# LoRa_RFM98W_Shield.net
KiCad netlist of a schematic drawn in EAGLE
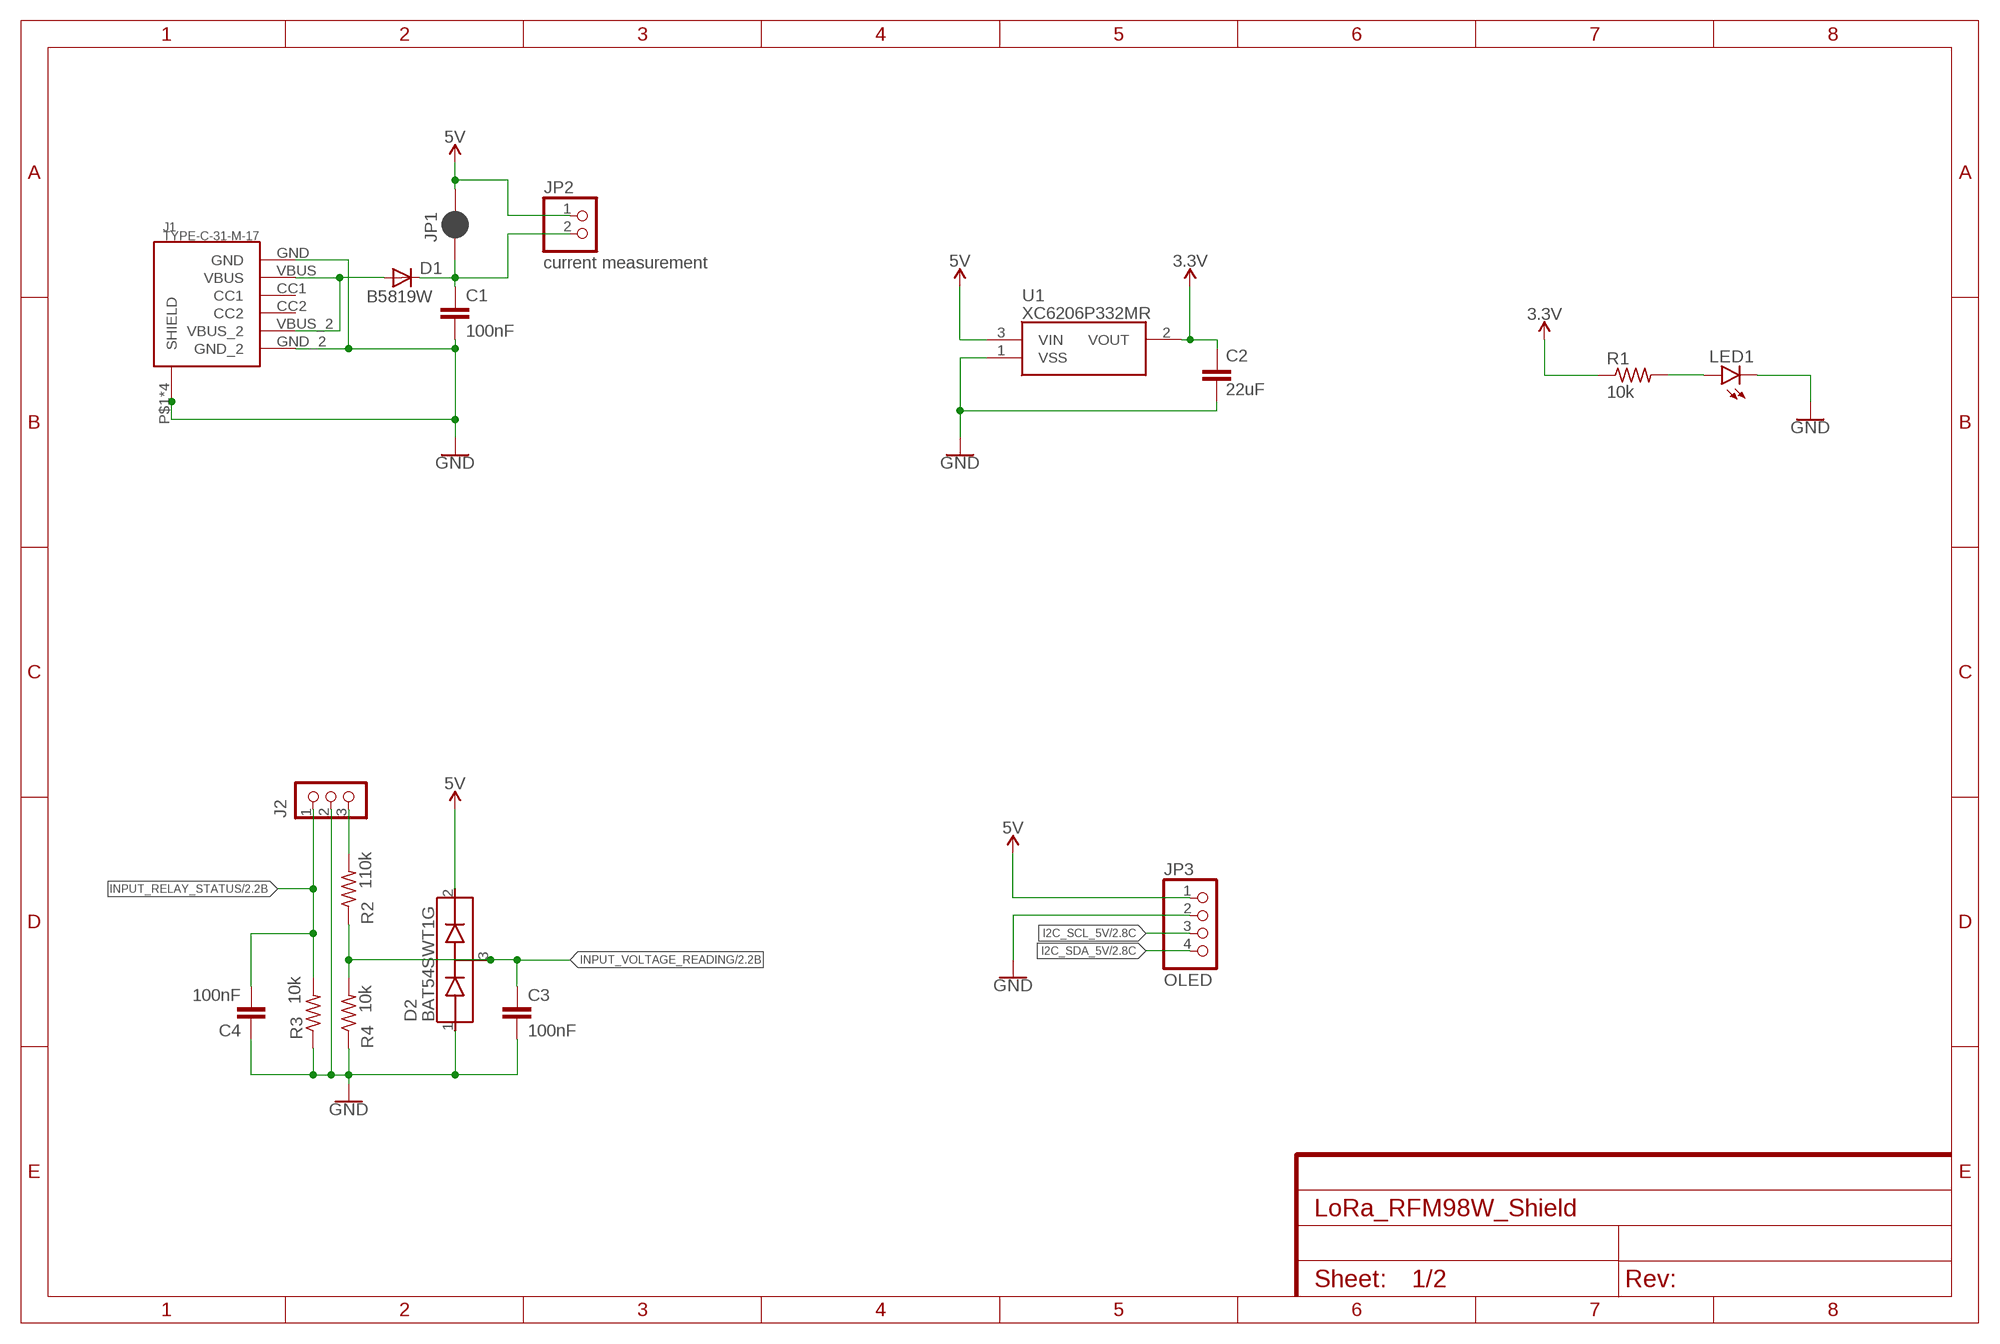
[diagram p0: schematic, sheet 1]
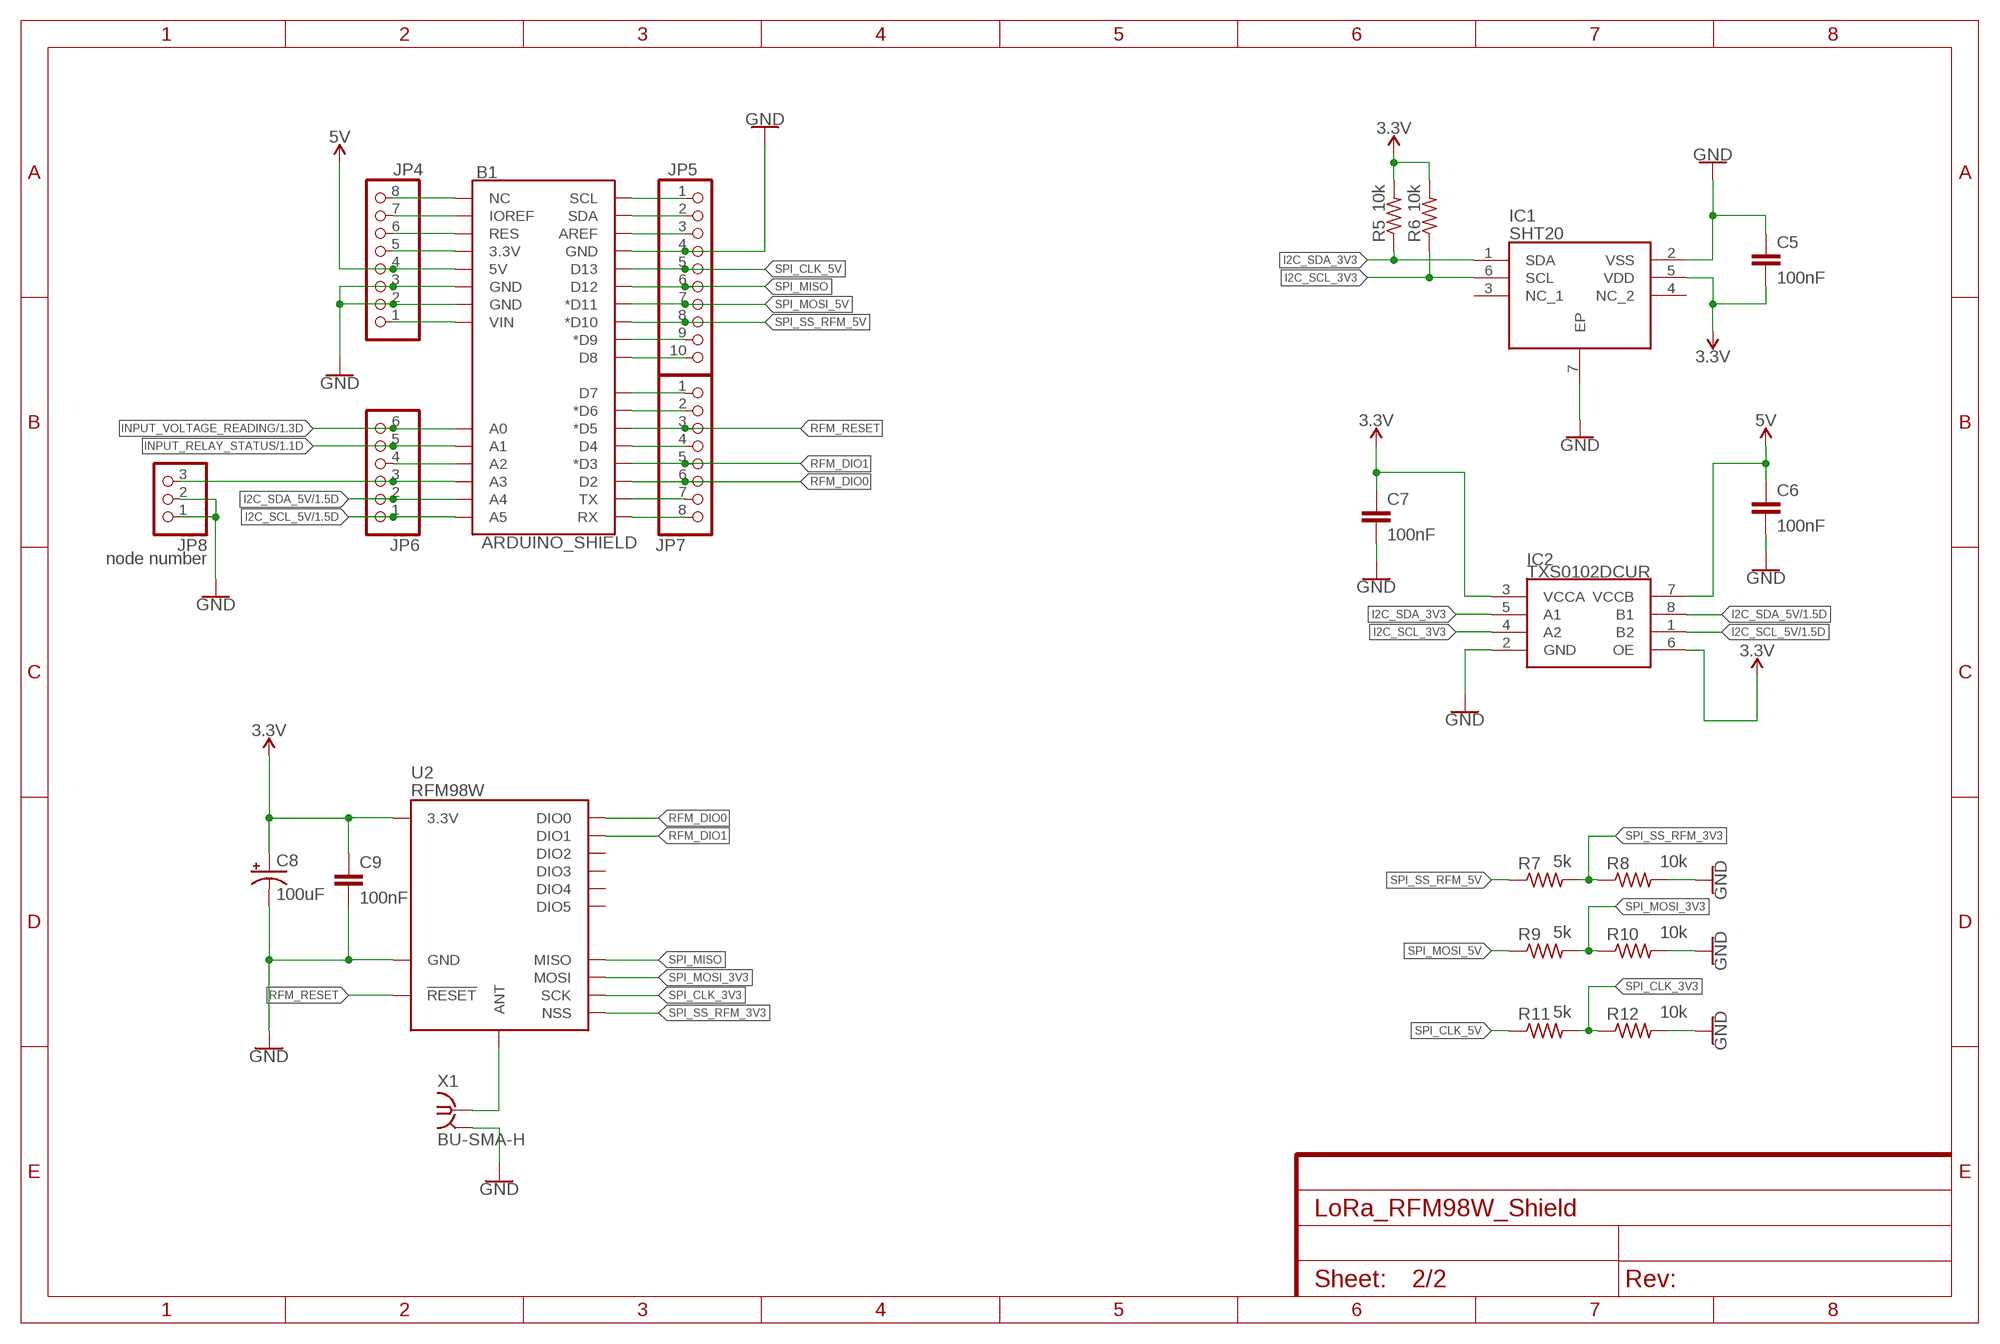
[diagram p1: schematic, sheet 2]

(export (version "E")
  (design (tool "Eeschema 10.0.6"))
  (components
    (comp (ref "B1")
      (value "ARDUINO_SHIELD")
      (footprint "eagle-import:UNO_R3_SHIELD_NOLABELS_LOCK")
      (libsource (lib "eagle-import") (part "ARDUINO_UNO_R3_SHIELDUNO_R3_SHIELD_NOLABELS_LOCK"))
    )
    (comp (ref "C5")
      (value "100nF")
      (footprint "eagle-import:C0603")
      (libsource (lib "eagle-import") (part "C-EUC0603"))
    )
    (comp (ref "C6")
      (value "100nF")
      (footprint "eagle-import:C0603")
      (libsource (lib "eagle-import") (part "C-EUC0603"))
    )
    (comp (ref "C7")
      (value "100nF")
      (footprint "eagle-import:C0603")
      (libsource (lib "eagle-import") (part "C-EUC0603"))
    )
    (comp (ref "C8")
      (value "100uF")
      (footprint "eagle-import:SMC_B")
      (libsource (lib "eagle-import") (part "CPOL-USSMCB"))
    )
    (comp (ref "C9")
      (value "100nF")
      (footprint "eagle-import:C0603")
      (libsource (lib "eagle-import") (part "C-EUC0603"))
    )
    (comp (ref "IC1")
      (value "SHT20")
      (footprint "eagle-import:SON100P300X300X110-7N")
      (fields (field (name "LCSC_PART_NUMBER") "C53865"))
      (libsource (lib "eagle-import") (part "SHT20"))
    )
    (comp (ref "IC2")
      (value "TXS0102DCUR")
      (footprint "eagle-import:SOP50P310X90-8N")
      (fields (field (name "LCSC_PART_NUMBER") "C53434"))
      (libsource (lib "eagle-import") (part "TXS0102DCUR"))
    )
    (comp (ref "JP4")
      (value "PINHD-1X8/OCT")
      (footprint "eagle-import:1X08_OCT")
      (libsource (lib "eagle-import") (part "PINHD-1X8/OCT"))
    )
    (comp (ref "JP5")
      (value "PINHD-1X10/OCT")
      (footprint "eagle-import:1X10_OCT")
      (libsource (lib "eagle-import") (part "PINHD-1X10/OCT"))
    )
    (comp (ref "JP6")
      (value "PINHD-1X6/OCT")
      (footprint "eagle-import:1X06_OCT")
      (libsource (lib "eagle-import") (part "PINHD-1X6/OCT"))
    )
    (comp (ref "JP7")
      (value "PINHD-1X8/OCT")
      (footprint "eagle-import:1X08_OCT")
      (libsource (lib "eagle-import") (part "PINHD-1X8/OCT"))
    )
    (comp (ref "JP8")
      (value "node number")
      (footprint "eagle-import:1X03_OCT")
      (libsource (lib "eagle-import") (part "PINHD-1X3/OCT"))
    )
    (comp (ref "R5")
      (value "10k")
      (footprint "eagle-import:R0603")
      (libsource (lib "eagle-import") (part "R-US_R0603"))
    )
    (comp (ref "R6")
      (value "10k")
      (footprint "eagle-import:R0603")
      (libsource (lib "eagle-import") (part "R-US_R0603"))
    )
    (comp (ref "R7")
      (value "5k")
      (footprint "eagle-import:R0603")
      (libsource (lib "eagle-import") (part "R-US_R0603"))
    )
    (comp (ref "R8")
      (value "10k")
      (footprint "eagle-import:R0603")
      (libsource (lib "eagle-import") (part "R-US_R0603"))
    )
    (comp (ref "R9")
      (value "5k")
      (footprint "eagle-import:R0603")
      (libsource (lib "eagle-import") (part "R-US_R0603"))
    )
    (comp (ref "R10")
      (value "10k")
      (footprint "eagle-import:R0603")
      (libsource (lib "eagle-import") (part "R-US_R0603"))
    )
    (comp (ref "R11")
      (value "5k")
      (footprint "eagle-import:R0603")
      (libsource (lib "eagle-import") (part "R-US_R0603"))
    )
    (comp (ref "R12")
      (value "10k")
      (footprint "eagle-import:R0603")
      (libsource (lib "eagle-import") (part "R-US_R0603"))
    )
    (comp (ref "U2")
      (value "RFM98W")
      (footprint "eagle-import:RFM95_96_97_98W")
      (libsource (lib "eagle-import") (part "RFM95W"))
    )
    (comp (ref "X1")
      (value "BU-SMA-H")
      (footprint "eagle-import:BU-SMA-H")
      (libsource (lib "eagle-import") (part "BU-SMA-H"))
    )
    (comp (ref "C1")
      (value "100nF")
      (footprint "eagle-import:C0603")
      (libsource (lib "eagle-import") (part "C-EUC0603"))
    )
    (comp (ref "C2")
      (value "22uF")
      (footprint "eagle-import:C0805")
      (libsource (lib "eagle-import") (part "C-EUC0805"))
    )
    (comp (ref "C3")
      (value "100nF")
      (footprint "eagle-import:C0603")
      (libsource (lib "eagle-import") (part "C-EUC0603"))
    )
    (comp (ref "C4")
      (value "100nF")
      (footprint "eagle-import:C0603")
      (libsource (lib "eagle-import") (part "C-EUC0603"))
    )
    (comp (ref "D1")
      (value "B5819W")
      (footprint "eagle-import:SOD-123")
      (libsource (lib "eagle-import") (part "DIODE-SOD-123"))
    )
    (comp (ref "D2")
      (value "BAT54SWT1G")
      (footprint "eagle-import:SOT65P220X100-3N")
      (fields (field (name "LCSC_PART_NUMBER") "C78260"))
      (libsource (lib "eagle-import") (part "BAT54SWT1G"))
    )
    (comp (ref "J1")
      (value "TYPE-C-31-M-17")
      (footprint "eagle-import:TYPE-C-31-M-17")
      (libsource (lib "eagle-import") (part "TYPE-C-31-M-17"))
    )
    (comp (ref "J2")
      (value "CON_TERMINAL_BLOCK_03-5MM")
      (footprint "eagle-import:TERMINAL_BLOCK_3P_5")
      (libsource (lib "eagle-import") (part "CON_TERMINAL_BLOCK_03-5MM"))
    )
    (comp (ref "JP1")
      (value "JUMPER-SMT_2_NC_PASTE_SILK")
      (footprint "eagle-import:SMT-JUMPER_2_NC_PASTE_SILK")
      (libsource (lib "eagle-import") (part "JUMPER-SMT_2_NC_PASTE_SILK"))
    )
    (comp (ref "JP2")
      (value "current measurement")
      (footprint "eagle-import:1X02_OCT")
      (libsource (lib "eagle-import") (part "PINHD-1X2/OCT"))
    )
    (comp (ref "JP3")
      (value "OLED")
      (footprint "eagle-import:1X04_OCT")
      (libsource (lib "eagle-import") (part "PINHD-1X4/OCT"))
    )
    (comp (ref "LED1")
      (value "LEDCHIPLED_0805")
      (footprint "eagle-import:CHIPLED_0805")
      (libsource (lib "eagle-import") (part "LEDCHIPLED_0805"))
    )
    (comp (ref "R1")
      (value "10k")
      (footprint "eagle-import:R0603")
      (libsource (lib "eagle-import") (part "R-US_R0603"))
    )
    (comp (ref "R2")
      (value "110k")
      (footprint "eagle-import:R0603")
      (libsource (lib "eagle-import") (part "R-US_R0603"))
    )
    (comp (ref "R3")
      (value "10k")
      (footprint "eagle-import:R0603")
      (libsource (lib "eagle-import") (part "R-US_R0603"))
    )
    (comp (ref "R4")
      (value "10k")
      (footprint "eagle-import:R0603")
      (libsource (lib "eagle-import") (part "R-US_R0603"))
    )
    (comp (ref "U1")
      (value "XC6206P332MR")
      (footprint "eagle-import:SOT95P280X130-3N")
      (libsource (lib "eagle-import") (part "XC6206P332MR"))
    )
  )
  (nets
    (net (code "1") (name "3.3V") (class "Default")
      (node (ref "C2") (pin "2") (pinfunction "2_2") (pintype "passive"))
      (node (ref "C5") (pin "2") (pinfunction "2_2") (pintype "passive"))
      (node (ref "C7") (pin "1") (pinfunction "1_1") (pintype "passive"))
      (node (ref "C8") (pin "+") (pinfunction "+_+") (pintype "passive"))
      (node (ref "C9") (pin "1") (pinfunction "1_1") (pintype "passive"))
      (node (ref "IC1") (pin "5") (pinfunction "VDD_5") (pintype "bidirectional"))
      (node (ref "IC2") (pin "3") (pinfunction "VCCA_3") (pintype "bidirectional"))
      (node (ref "IC2") (pin "6") (pinfunction "OE_6") (pintype "bidirectional"))
      (node (ref "R1") (pin "1") (pinfunction "1_1") (pintype "passive"))
      (node (ref "R5") (pin "2") (pinfunction "2_2") (pintype "passive"))
      (node (ref "R6") (pin "2") (pinfunction "2_2") (pintype "passive"))
      (node (ref "U1") (pin "2") (pinfunction "VOUT_2") (pintype "output"))
      (node (ref "U2") (pin "3.3V") (pinfunction "3.3V_3.3V") (pintype "bidirectional"))
    )
    (net (code "2") (name "5V") (class "Default")
      (node (ref "B1") (pin "5V") (pinfunction "5V_5V") (pintype "bidirectional"))
      (node (ref "C6") (pin "1") (pinfunction "1_1") (pintype "passive"))
      (node (ref "D2") (pin "2") (pinfunction "CATHODE_2") (pintype "bidirectional"))
      (node (ref "IC2") (pin "7") (pinfunction "VCCB_7") (pintype "bidirectional"))
      (node (ref "JP1") (pin "2") (pinfunction "2_2") (pintype "passive"))
      (node (ref "JP2") (pin "1") (pinfunction "1_1") (pintype "passive"))
      (node (ref "JP3") (pin "1") (pinfunction "1_1") (pintype "passive"))
      (node (ref "JP4") (pin "4") (pinfunction "4_4") (pintype "passive"))
      (node (ref "U1") (pin "3") (pinfunction "VIN_3") (pintype "input"))
    )
    (net (code "3") (name "GND") (class "Default")
      (node (ref "B1") (pin "GND@0") (pinfunction "GND_GND@0") (pintype "bidirectional"))
      (node (ref "B1") (pin "GND@1") (pinfunction "GND_GND@1") (pintype "bidirectional"))
      (node (ref "B1") (pin "GND@2") (pinfunction "GND_GND@2") (pintype "bidirectional"))
      (node (ref "C1") (pin "2") (pinfunction "2_2") (pintype "passive"))
      (node (ref "C2") (pin "1") (pinfunction "1_1") (pintype "passive"))
      (node (ref "C3") (pin "2") (pinfunction "2_2") (pintype "passive"))
      (node (ref "C4") (pin "1") (pinfunction "1_1") (pintype "passive"))
      (node (ref "C5") (pin "1") (pinfunction "1_1") (pintype "passive"))
      (node (ref "C6") (pin "2") (pinfunction "2_2") (pintype "passive"))
      (node (ref "C7") (pin "2") (pinfunction "2_2") (pintype "passive"))
      (node (ref "C8") (pin "-") (pinfunction "-_-") (pintype "passive"))
      (node (ref "C9") (pin "2") (pinfunction "2_2") (pintype "passive"))
      (node (ref "D2") (pin "1") (pinfunction "ANODE_1") (pintype "bidirectional"))
      (node (ref "IC1") (pin "2") (pinfunction "VSS_2") (pintype "bidirectional"))
      (node (ref "IC1") (pin "7") (pinfunction "EP_7") (pintype "bidirectional"))
      (node (ref "IC2") (pin "2") (pinfunction "GND_2") (pintype "bidirectional"))
      (node (ref "J1") (pin "GND") (pinfunction "GND_GND") (pintype "bidirectional"))
      (node (ref "J1") (pin "GND_2") (pinfunction "GND_2_GND_2") (pintype "bidirectional"))
      (node (ref "J1") (pin "P$1") (pinfunction "SHIELD_P$1") (pintype "bidirectional"))
      (node (ref "J1") (pin "P$2") (pinfunction "SHIELD_P$2") (pintype "bidirectional"))
      (node (ref "J1") (pin "P$3") (pinfunction "SHIELD_P$3") (pintype "bidirectional"))
      (node (ref "J1") (pin "P$4") (pinfunction "SHIELD_P$4") (pintype "bidirectional"))
      (node (ref "J2") (pin "2") (pinfunction "2_2") (pintype "bidirectional"))
      (node (ref "JP3") (pin "2") (pinfunction "2_2") (pintype "passive"))
      (node (ref "JP4") (pin "2") (pinfunction "2_2") (pintype "passive"))
      (node (ref "JP4") (pin "3") (pinfunction "3_3") (pintype "passive"))
      (node (ref "JP5") (pin "4") (pinfunction "4_4") (pintype "passive"))
      (node (ref "JP8") (pin "1") (pinfunction "1_1") (pintype "passive"))
      (node (ref "JP8") (pin "2") (pinfunction "2_2") (pintype "passive"))
      (node (ref "LED1") (pin "C") (pinfunction "C_C") (pintype "passive"))
      (node (ref "R10") (pin "2") (pinfunction "2_2") (pintype "passive"))
      (node (ref "R12") (pin "2") (pinfunction "2_2") (pintype "passive"))
      (node (ref "R3") (pin "1") (pinfunction "1_1") (pintype "passive"))
      (node (ref "R4") (pin "1") (pinfunction "1_1") (pintype "passive"))
      (node (ref "R8") (pin "2") (pinfunction "2_2") (pintype "passive"))
      (node (ref "U1") (pin "1") (pinfunction "VSS_1") (pintype "power_in"))
      (node (ref "U2") (pin "GND@1") (pinfunction "GND_GND@1") (pintype "bidirectional"))
      (node (ref "U2") (pin "GND@2") (pinfunction "GND_GND@2") (pintype "bidirectional"))
      (node (ref "U2") (pin "GND@3") (pinfunction "GND_GND@3") (pintype "bidirectional"))
      (node (ref "X1") (pin "2") (pinfunction "2_2") (pintype "passive"))
      (node (ref "X1") (pin "3") (pinfunction "2_3") (pintype "passive"))
      (node (ref "X1") (pin "4") (pinfunction "2_4") (pintype "passive"))
      (node (ref "X1") (pin "5") (pinfunction "2_5") (pintype "passive"))
    )
    (net (code "4") (name "I2C_SCL_3V3") (class "Default")
      (node (ref "IC1") (pin "6") (pinfunction "SCL_6") (pintype "bidirectional"))
      (node (ref "IC2") (pin "4") (pinfunction "A2_4") (pintype "bidirectional"))
      (node (ref "R6") (pin "1") (pinfunction "1_1") (pintype "passive"))
    )
    (net (code "5") (name "I2C_SCL_5V") (class "Default")
      (node (ref "B1") (pin "A5") (pinfunction "A5_A5") (pintype "bidirectional"))
      (node (ref "IC2") (pin "1") (pinfunction "B2_1") (pintype "bidirectional"))
      (node (ref "JP3") (pin "3") (pinfunction "3_3") (pintype "passive"))
      (node (ref "JP6") (pin "1") (pinfunction "1_1") (pintype "passive"))
    )
    (net (code "6") (name "I2C_SDA_3V3") (class "Default")
      (node (ref "IC1") (pin "1") (pinfunction "SDA_1") (pintype "bidirectional"))
      (node (ref "IC2") (pin "5") (pinfunction "A1_5") (pintype "bidirectional"))
      (node (ref "R5") (pin "1") (pinfunction "1_1") (pintype "passive"))
    )
    (net (code "7") (name "I2C_SDA_5V") (class "Default")
      (node (ref "B1") (pin "A4") (pinfunction "A4_A4") (pintype "bidirectional"))
      (node (ref "IC2") (pin "8") (pinfunction "B1_8") (pintype "bidirectional"))
      (node (ref "JP3") (pin "4") (pinfunction "4_4") (pintype "passive"))
      (node (ref "JP6") (pin "2") (pinfunction "2_2") (pintype "passive"))
    )
    (net (code "8") (name "INPUT_RELAY_STATUS") (class "Default")
      (node (ref "B1") (pin "A1") (pinfunction "A1_A1") (pintype "bidirectional"))
      (node (ref "C4") (pin "2") (pinfunction "2_2") (pintype "passive"))
      (node (ref "J2") (pin "1") (pinfunction "1_1") (pintype "bidirectional"))
      (node (ref "JP6") (pin "5") (pinfunction "5_5") (pintype "passive"))
      (node (ref "R3") (pin "2") (pinfunction "2_2") (pintype "passive"))
    )
    (net (code "9") (name "INPUT_VOLTAGE_READING") (class "Default")
      (node (ref "B1") (pin "A0") (pinfunction "A0_A0") (pintype "bidirectional"))
      (node (ref "C3") (pin "1") (pinfunction "1_1") (pintype "passive"))
      (node (ref "D2") (pin "3") (pinfunction "CATHODE-ANODE_3") (pintype "bidirectional"))
      (node (ref "JP6") (pin "6") (pinfunction "6_6") (pintype "passive"))
      (node (ref "R2") (pin "1") (pinfunction "1_1") (pintype "passive"))
      (node (ref "R4") (pin "2") (pinfunction "2_2") (pintype "passive"))
    )
    (net (code "10") (name "Net-(B1-*D6)") (class "Default")
      (node (ref "B1") (pin "D6") (pinfunction "*D6_D6") (pintype "bidirectional"))
      (node (ref "JP7") (pin "2") (pinfunction "2_2") (pintype "passive"))
    )
    (net (code "11") (name "Net-(B1-*D9)") (class "Default")
      (node (ref "B1") (pin "D9") (pinfunction "*D9_D9") (pintype "bidirectional"))
      (node (ref "JP5") (pin "9") (pinfunction "9_9") (pintype "passive"))
    )
    (net (code "12") (name "Net-(B1-Pad3.3V)") (class "Default")
      (node (ref "B1") (pin "3.3V") (pinfunction "3.3V_3.3V") (pintype "bidirectional"))
      (node (ref "JP4") (pin "5") (pinfunction "5_5") (pintype "passive"))
    )
    (net (code "13") (name "Net-(B1-PadA2)") (class "Default")
      (node (ref "B1") (pin "A2") (pinfunction "A2_A2") (pintype "bidirectional"))
      (node (ref "JP6") (pin "4") (pinfunction "4_4") (pintype "passive"))
    )
    (net (code "14") (name "Net-(B1-PadA3)") (class "Default")
      (node (ref "B1") (pin "A3") (pinfunction "A3_A3") (pintype "bidirectional"))
      (node (ref "JP6") (pin "3") (pinfunction "3_3") (pintype "passive"))
      (node (ref "JP8") (pin "3") (pinfunction "3_3") (pintype "passive"))
    )
    (net (code "15") (name "Net-(B1-PadAREF)") (class "Default")
      (node (ref "B1") (pin "AREF") (pinfunction "AREF_AREF") (pintype "bidirectional"))
      (node (ref "JP5") (pin "3") (pinfunction "3_3") (pintype "passive"))
    )
    (net (code "16") (name "Net-(B1-PadD4)") (class "Default")
      (node (ref "B1") (pin "D4") (pinfunction "D4_D4") (pintype "bidirectional"))
      (node (ref "JP7") (pin "4") (pinfunction "4_4") (pintype "passive"))
    )
    (net (code "17") (name "Net-(B1-PadD7)") (class "Default")
      (node (ref "B1") (pin "D7") (pinfunction "D7_D7") (pintype "bidirectional"))
      (node (ref "JP7") (pin "1") (pinfunction "1_1") (pintype "passive"))
    )
    (net (code "18") (name "Net-(B1-PadD8)") (class "Default")
      (node (ref "B1") (pin "D8") (pinfunction "D8_D8") (pintype "bidirectional"))
      (node (ref "JP5") (pin "10") (pinfunction "10_10") (pintype "passive"))
    )
    (net (code "19") (name "Net-(B1-PadIOREF)") (class "Default")
      (node (ref "B1") (pin "IOREF") (pinfunction "IOREF_IOREF") (pintype "bidirectional"))
      (node (ref "JP4") (pin "7") (pinfunction "7_7") (pintype "passive"))
    )
    (net (code "20") (name "Net-(B1-PadNC)") (class "Default")
      (node (ref "B1") (pin "NC") (pinfunction "NC_NC") (pintype "bidirectional"))
      (node (ref "JP4") (pin "8") (pinfunction "8_8") (pintype "passive"))
    )
    (net (code "21") (name "Net-(B1-PadRES)") (class "Default")
      (node (ref "B1") (pin "RES") (pinfunction "RES_RES") (pintype "bidirectional"))
      (node (ref "JP4") (pin "6") (pinfunction "6_6") (pintype "passive"))
    )
    (net (code "22") (name "Net-(B1-PadRX)") (class "Default")
      (node (ref "B1") (pin "RX") (pinfunction "RX_RX") (pintype "bidirectional"))
      (node (ref "JP7") (pin "8") (pinfunction "8_8") (pintype "passive"))
    )
    (net (code "23") (name "Net-(B1-PadSCL)") (class "Default")
      (node (ref "B1") (pin "SCL") (pinfunction "SCL_SCL") (pintype "bidirectional"))
      (node (ref "JP5") (pin "1") (pinfunction "1_1") (pintype "passive"))
    )
    (net (code "24") (name "Net-(B1-PadSDA)") (class "Default")
      (node (ref "B1") (pin "SDA") (pinfunction "SDA_SDA") (pintype "bidirectional"))
      (node (ref "JP5") (pin "2") (pinfunction "2_2") (pintype "passive"))
    )
    (net (code "25") (name "Net-(B1-PadTX)") (class "Default")
      (node (ref "B1") (pin "TX") (pinfunction "TX_TX") (pintype "bidirectional"))
      (node (ref "JP7") (pin "7") (pinfunction "7_7") (pintype "passive"))
    )
    (net (code "26") (name "Net-(B1-PadVIN)") (class "Default")
      (node (ref "B1") (pin "VIN") (pinfunction "VIN_VIN") (pintype "bidirectional"))
      (node (ref "JP4") (pin "1") (pinfunction "1_1") (pintype "passive"))
    )
    (net (code "27") (name "Net-(C1-Pad1)") (class "Default")
      (node (ref "C1") (pin "1") (pinfunction "1_1") (pintype "passive"))
      (node (ref "D1") (pin "C") (pinfunction "C_C") (pintype "passive"))
      (node (ref "JP1") (pin "1") (pinfunction "1_1") (pintype "passive"))
      (node (ref "JP2") (pin "2") (pinfunction "2_2") (pintype "passive"))
    )
    (net (code "28") (name "Net-(D1-PadA)") (class "Default")
      (node (ref "D1") (pin "A") (pinfunction "A_A") (pintype "passive"))
      (node (ref "J1") (pin "VBUS") (pinfunction "VBUS_VBUS") (pintype "bidirectional"))
      (node (ref "J1") (pin "VBUS_2") (pinfunction "VBUS_2_VBUS_2") (pintype "bidirectional"))
    )
    (net (code "29") (name "Net-(J2-Pad3)") (class "Default")
      (node (ref "J2") (pin "3") (pinfunction "3_3") (pintype "bidirectional"))
      (node (ref "R2") (pin "2") (pinfunction "2_2") (pintype "passive"))
    )
    (net (code "30") (name "Net-(LED1-PadA)") (class "Default")
      (node (ref "LED1") (pin "A") (pinfunction "A_A") (pintype "passive"))
      (node (ref "R1") (pin "2") (pinfunction "2_2") (pintype "passive"))
    )
    (net (code "31") (name "Net-(U2-PadANT)") (class "Default")
      (node (ref "U2") (pin "ANT") (pinfunction "ANT_ANT") (pintype "bidirectional"))
      (node (ref "X1") (pin "1") (pinfunction "1_1") (pintype "passive"))
    )
    (net (code "32") (name "RFM_DIO0") (class "Default")
      (node (ref "B1") (pin "D2") (pinfunction "D2_D2") (pintype "bidirectional"))
      (node (ref "JP7") (pin "6") (pinfunction "6_6") (pintype "passive"))
      (node (ref "U2") (pin "DIO0") (pinfunction "DIO0_DIO0") (pintype "bidirectional"))
    )
    (net (code "33") (name "RFM_DIO1") (class "Default")
      (node (ref "B1") (pin "D3") (pinfunction "*D3_D3") (pintype "bidirectional"))
      (node (ref "JP7") (pin "5") (pinfunction "5_5") (pintype "passive"))
      (node (ref "U2") (pin "DIO1") (pinfunction "DIO1_DIO1") (pintype "bidirectional"))
    )
    (net (code "34") (name "RFM_RESET") (class "Default")
      (node (ref "B1") (pin "D5") (pinfunction "*D5_D5") (pintype "bidirectional"))
      (node (ref "JP7") (pin "3") (pinfunction "3_3") (pintype "passive"))
      (node (ref "U2") (pin "!RESET") (pinfunction "~{RESET}_!RESET") (pintype "bidirectional"))
    )
    (net (code "35") (name "SPI_CLK_3V3") (class "Default")
      (node (ref "R11") (pin "2") (pinfunction "2_2") (pintype "passive"))
      (node (ref "R12") (pin "1") (pinfunction "1_1") (pintype "passive"))
      (node (ref "U2") (pin "SCK") (pinfunction "SCK_SCK") (pintype "bidirectional"))
    )
    (net (code "36") (name "SPI_CLK_5V") (class "Default")
      (node (ref "B1") (pin "D13") (pinfunction "D13_D13") (pintype "bidirectional"))
      (node (ref "JP5") (pin "5") (pinfunction "5_5") (pintype "passive"))
      (node (ref "R11") (pin "1") (pinfunction "1_1") (pintype "passive"))
    )
    (net (code "37") (name "SPI_MISO") (class "Default")
      (node (ref "B1") (pin "D12") (pinfunction "D12_D12") (pintype "bidirectional"))
      (node (ref "JP5") (pin "6") (pinfunction "6_6") (pintype "passive"))
      (node (ref "U2") (pin "MISO") (pinfunction "MISO_MISO") (pintype "bidirectional"))
    )
    (net (code "38") (name "SPI_MOSI_3V3") (class "Default")
      (node (ref "R10") (pin "1") (pinfunction "1_1") (pintype "passive"))
      (node (ref "R9") (pin "2") (pinfunction "2_2") (pintype "passive"))
      (node (ref "U2") (pin "MOSI") (pinfunction "MOSI_MOSI") (pintype "bidirectional"))
    )
    (net (code "39") (name "SPI_MOSI_5V") (class "Default")
      (node (ref "B1") (pin "D11") (pinfunction "*D11_D11") (pintype "bidirectional"))
      (node (ref "JP5") (pin "7") (pinfunction "7_7") (pintype "passive"))
      (node (ref "R9") (pin "1") (pinfunction "1_1") (pintype "passive"))
    )
    (net (code "40") (name "SPI_SS_RFM_3V3") (class "Default")
      (node (ref "R7") (pin "2") (pinfunction "2_2") (pintype "passive"))
      (node (ref "R8") (pin "1") (pinfunction "1_1") (pintype "passive"))
      (node (ref "U2") (pin "NSS") (pinfunction "NSS_NSS") (pintype "bidirectional"))
    )
    (net (code "41") (name "SPI_SS_RFM_5V") (class "Default")
      (node (ref "B1") (pin "D10") (pinfunction "*D10_D10") (pintype "bidirectional"))
      (node (ref "JP5") (pin "8") (pinfunction "8_8") (pintype "passive"))
      (node (ref "R7") (pin "1") (pinfunction "1_1") (pintype "passive"))
    )
    (net (code "42") (name "unconnected-(IC1-NC_1-Pad3)") (class "Default")
      (node (ref "IC1") (pin "3") (pinfunction "NC_1_3") (pintype "bidirectional"))
    )
    (net (code "43") (name "unconnected-(IC1-NC_2-Pad4)") (class "Default")
      (node (ref "IC1") (pin "4") (pinfunction "NC_2_4") (pintype "bidirectional"))
    )
    (net (code "44") (name "unconnected-(J1-PadCC1)") (class "Default")
      (node (ref "J1") (pin "CC1") (pinfunction "CC1_CC1") (pintype "bidirectional"))
    )
    (net (code "45") (name "unconnected-(J1-PadCC2)") (class "Default")
      (node (ref "J1") (pin "CC2") (pinfunction "CC2_CC2") (pintype "bidirectional"))
    )
    (net (code "46") (name "unconnected-(U2-PadDIO2)") (class "Default")
      (node (ref "U2") (pin "DIO2") (pinfunction "DIO2_DIO2") (pintype "bidirectional"))
    )
    (net (code "47") (name "unconnected-(U2-PadDIO3)") (class "Default")
      (node (ref "U2") (pin "DIO3") (pinfunction "DIO3_DIO3") (pintype "bidirectional"))
    )
    (net (code "48") (name "unconnected-(U2-PadDIO4)") (class "Default")
      (node (ref "U2") (pin "DIO4") (pinfunction "DIO4_DIO4") (pintype "bidirectional"))
    )
    (net (code "49") (name "unconnected-(U2-PadDIO5)") (class "Default")
      (node (ref "U2") (pin "DIO5") (pinfunction "DIO5_DIO5") (pintype "bidirectional"))
    )
  )
)
